# MicroDial_Data_Log_V2_Part2.net
KiCad netlist of a schematic drawn in Altium Designer
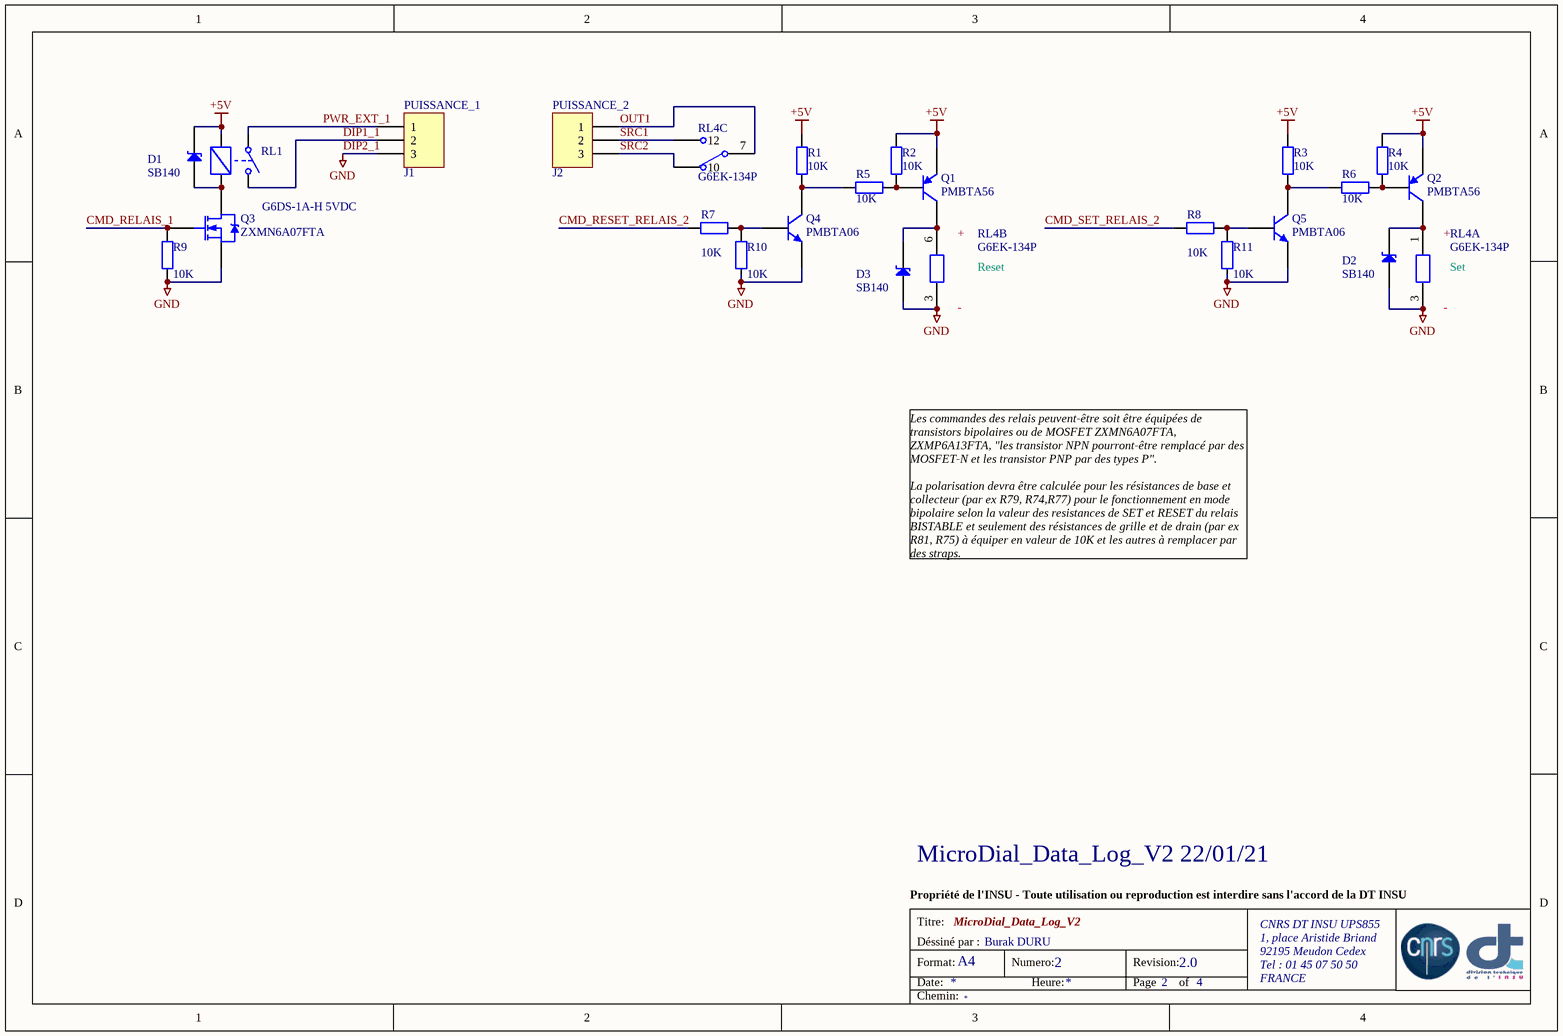
[diagram p0: MicroDial_Data_Log_V2_Part2.SchDoc]

(export (version "E")
  (design (tool "Eeschema 10.0.6"))
  (components
    (comp (ref "D1")
      (value "SB140")
      (footprint "DO-41")
      (description "SB140  Redresseur Schottky, 40 V, 1 A, Une, DO-41 (DO-204AL), 2 Broche(s), 500 mV")
      (libsource (lib "pSDLA") (part "Diode_Schottky"))
    )
    (comp (ref "D2")
      (value "SB140")
      (footprint "DO-41")
      (description "SB140  Redresseur Schottky, 40 V, 1 A, Une, DO-41 (DO-204AL), 2 Broche(s), 500 mV")
      (libsource (lib "pSDLA") (part "Diode_Schottky"))
    )
    (comp (ref "D3")
      (value "SB140")
      (footprint "DO-41")
      (description "SB140  Redresseur Schottky, 40 V, 1 A, Une, DO-41 (DO-204AL), 2 Broche(s), 500 mV")
      (libsource (lib "pSDLA") (part "Diode_Schottky"))
    )
    (comp (ref "J1")
      (value "PUISSANCE_1")
      (footprint "MKDS 1/3-3.81")
      (description "PHOENIX CONTACT MKDS 1/3-3.81  SR 3V DROIT")
      (libsource (lib "") (part "PHOENIX CONTACT MKDS 1/3-3.81_1"))
    )
    (comp (ref "J2")
      (value "PUISSANCE_2")
      (footprint "MKDS 1/3-3.81")
      (description "PHOENIX CONTACT MKDS 1/3-3.81  SR 3V DROIT")
      (libsource (lib "pSDLA") (part "PHOENIX CONTACT MKDS 1/3-3.81"))
    )
    (comp (ref "Q1")
      (value "PMBTA56")
      (footprint "PSDLA:SOT-23A")
      (description "PNP General Purpose Amplifier")
      (libsource (lib "pSDLA") (part "PMBTA56"))
    )
    (comp (ref "Q2")
      (value "PMBTA56")
      (footprint "PSDLA:SOT-23A")
      (description "PNP General Purpose Amplifier")
      (libsource (lib "pSDLA") (part "PMBTA56"))
    )
    (comp (ref "Q3")
      (value "ZXMN6A07FTA")
      (footprint "SOT23 - NMOSFET")
      (description "60V N-Channel ENHANCEMENT MODE MOSFET")
      (libsource (lib "pSDLA") (part "ZXMN6A07FTA"))
    )
    (comp (ref "Q4")
      (value "PMBTA06")
      (footprint "SOT-23A")
      (description "NPN General Purpose Amplifier")
      (libsource (lib "pSDLA") (part "PMBTA06"))
    )
    (comp (ref "Q5")
      (value "PMBTA06")
      (footprint "SOT-23A")
      (description "NPN General Purpose Amplifier")
      (libsource (lib "pSDLA") (part "PMBTA06"))
    )
    (comp (ref "R1")
      (value "10K")
      (footprint "R603")
      (fields (field (name "Comment") "Res"))
      (libsource (lib "pSDLA") (part "Res"))
    )
    (comp (ref "R2")
      (value "10K")
      (footprint "R603")
      (fields (field (name "Comment") "Res"))
      (libsource (lib "pSDLA") (part "Res"))
    )
    (comp (ref "R3")
      (value "10K")
      (footprint "R603")
      (fields (field (name "Comment") "Res"))
      (libsource (lib "pSDLA") (part "Res"))
    )
    (comp (ref "R4")
      (value "10K")
      (footprint "R603")
      (fields (field (name "Comment") "Res"))
      (libsource (lib "pSDLA") (part "Res"))
    )
    (comp (ref "R5")
      (value "10K")
      (footprint "R603")
      (fields (field (name "Comment") "Res"))
      (libsource (lib "") (part "Res_1"))
    )
    (comp (ref "R6")
      (value "10K")
      (footprint "R603")
      (fields (field (name "Comment") "Res"))
      (libsource (lib "") (part "Res_1"))
    )
    (comp (ref "R7")
      (value "10K")
      (footprint "R603")
      (fields (field (name "Comment") "Res"))
      (libsource (lib "") (part "Res_3"))
    )
    (comp (ref "R8")
      (value "10K")
      (footprint "R603")
      (fields (field (name "Comment") "Res"))
      (libsource (lib "") (part "Res_3"))
    )
    (comp (ref "R9")
      (value "10K")
      (footprint "R603")
      (fields (field (name "Comment") "Res"))
      (libsource (lib "") (part "Res_2"))
    )
    (comp (ref "R10")
      (value "10K")
      (footprint "R603")
      (fields (field (name "Comment") "Res"))
      (libsource (lib "") (part "Res_2"))
    )
    (comp (ref "R11")
      (value "10K")
      (footprint "R603")
      (fields (field (name "Comment") "Res"))
      (libsource (lib "") (part "Res_2"))
    )
    (comp (ref "RL1")
      (value "G6DS-1A-H 5VDC")
      (footprint "G6DS-1A-H")
      (description "Relais 1RT Normalement Ouvert 5V 5A")
      (libsource (lib "pSDLA") (part "G6DS-1A-H 5VDC"))
    )
    (comp (ref "RL4")
      (value "G6EK-134P")
      (footprint "G6EK-134P")
      (description "SPST RELAIS DOUBLE COIL")
      (libsource (lib "pSDLA") (part "G6EK-134P"))
    )
  )
  (nets
    (net (code "1") (name "+5V") (class "Default")
      (node (ref "D1") (pin "2") (pinfunction "K_2") (pintype "passive"))
      (node (ref "Q1") (pin "2") (pinfunction "E_2") (pintype "passive"))
      (node (ref "Q2") (pin "2") (pinfunction "E_2") (pintype "passive"))
      (node (ref "R1") (pin "1") (pinfunction "1_1") (pintype "passive"))
      (node (ref "R2") (pin "1") (pinfunction "1_1") (pintype "passive"))
      (node (ref "R3") (pin "1") (pinfunction "1_1") (pintype "passive"))
      (node (ref "R4") (pin "1") (pinfunction "1_1") (pintype "passive"))
      (node (ref "RL1") (pin "16") (pinfunction "16_16") (pintype "passive"))
    )
    (net (code "2") (name "/CMD_RELAIS_1") (class "Default")
      (node (ref "Q3") (pin "1") (pinfunction "G_1") (pintype "passive"))
      (node (ref "R9") (pin "2") (pinfunction "2_2") (pintype "passive"))
    )
    (net (code "3") (name "/CMD_RESET_RELAIS_2") (class "Default")
      (node (ref "R7") (pin "2") (pinfunction "2_2") (pintype "passive"))
    )
    (net (code "4") (name "/CMD_SET_RELAIS_2") (class "Default")
      (node (ref "R8") (pin "2") (pinfunction "2_2") (pintype "passive"))
    )
    (net (code "5") (name "/DIP1_1") (class "Default")
      (node (ref "J1") (pin "2") (pinfunction "2_2") (pintype "passive"))
      (node (ref "RL1") (pin "6") (pinfunction "6_6") (pintype "passive"))
    )
    (net (code "6") (name "/OUT1") (class "Default")
      (node (ref "J2") (pin "1") (pinfunction "1_1") (pintype "passive"))
      (node (ref "RL4") (pin "7") (pinfunction "7_7") (pintype "passive"))
    )
    (net (code "7") (name "/PWR_EXT_1") (class "Default")
      (node (ref "J1") (pin "1") (pinfunction "1_1") (pintype "passive"))
      (node (ref "RL1") (pin "8") (pinfunction "8_8") (pintype "passive"))
    )
    (net (code "8") (name "/SRC1") (class "Default")
      (node (ref "J2") (pin "2") (pinfunction "2_2") (pintype "passive"))
      (node (ref "RL4") (pin "12") (pinfunction "12_12") (pintype "passive"))
    )
    (net (code "9") (name "/SRC2") (class "Default")
      (node (ref "J2") (pin "3") (pinfunction "3_3") (pintype "passive"))
      (node (ref "RL4") (pin "10") (pinfunction "10_10") (pintype "passive"))
    )
    (net (code "10") (name "GND") (class "Default")
      (node (ref "D2") (pin "1") (pinfunction "A_1") (pintype "passive"))
      (node (ref "D3") (pin "1") (pinfunction "A_1") (pintype "passive"))
      (node (ref "J1") (pin "3") (pinfunction "3_3") (pintype "passive"))
      (node (ref "Q3") (pin "3") (pinfunction "S_3") (pintype "passive"))
      (node (ref "Q4") (pin "2") (pinfunction "E_2") (pintype "passive"))
      (node (ref "Q5") (pin "2") (pinfunction "E_2") (pintype "passive"))
      (node (ref "R10") (pin "1") (pinfunction "1_1") (pintype "passive"))
      (node (ref "R11") (pin "1") (pinfunction "1_1") (pintype "passive"))
      (node (ref "R9") (pin "1") (pinfunction "1_1") (pintype "passive"))
      (node (ref "RL4") (pin "3") (pinfunction "3_3") (pintype "passive"))
    )
    (net (code "11") (name "Net-(D1-A)") (class "Default")
      (node (ref "D1") (pin "1") (pinfunction "A_1") (pintype "passive"))
      (node (ref "Q3") (pin "2") (pinfunction "D_2") (pintype "passive"))
      (node (ref "RL1") (pin "15") (pinfunction "15_15") (pintype "passive"))
    )
    (net (code "12") (name "Net-(D2-K)") (class "Default")
      (node (ref "D2") (pin "2") (pinfunction "K_2") (pintype "passive"))
      (node (ref "Q2") (pin "3") (pinfunction "C_3") (pintype "passive"))
      (node (ref "RL4") (pin "1") (pinfunction "1_1") (pintype "passive"))
    )
    (net (code "13") (name "Net-(D3-K)") (class "Default")
      (node (ref "D3") (pin "2") (pinfunction "K_2") (pintype "passive"))
      (node (ref "Q1") (pin "3") (pinfunction "C_3") (pintype "passive"))
      (node (ref "RL4") (pin "6") (pinfunction "6_6") (pintype "passive"))
    )
    (net (code "14") (name "Net-(Q1-B)") (class "Default")
      (node (ref "Q1") (pin "1") (pinfunction "B_1") (pintype "passive"))
      (node (ref "R2") (pin "2") (pinfunction "2_2") (pintype "passive"))
      (node (ref "R5") (pin "2") (pinfunction "2_2") (pintype "passive"))
    )
    (net (code "15") (name "Net-(Q2-B)") (class "Default")
      (node (ref "Q2") (pin "1") (pinfunction "B_1") (pintype "passive"))
      (node (ref "R4") (pin "2") (pinfunction "2_2") (pintype "passive"))
      (node (ref "R6") (pin "2") (pinfunction "2_2") (pintype "passive"))
    )
    (net (code "16") (name "Net-(Q4-B)") (class "Default")
      (node (ref "Q4") (pin "1") (pinfunction "B_1") (pintype "passive"))
      (node (ref "R10") (pin "2") (pinfunction "2_2") (pintype "passive"))
      (node (ref "R7") (pin "1") (pinfunction "1_1") (pintype "passive"))
    )
    (net (code "17") (name "Net-(Q4-C)") (class "Default")
      (node (ref "Q4") (pin "3") (pinfunction "C_3") (pintype "passive"))
      (node (ref "R1") (pin "2") (pinfunction "2_2") (pintype "passive"))
      (node (ref "R5") (pin "1") (pinfunction "1_1") (pintype "passive"))
    )
    (net (code "18") (name "Net-(Q5-B)") (class "Default")
      (node (ref "Q5") (pin "1") (pinfunction "B_1") (pintype "passive"))
      (node (ref "R11") (pin "2") (pinfunction "2_2") (pintype "passive"))
      (node (ref "R8") (pin "1") (pinfunction "1_1") (pintype "passive"))
    )
    (net (code "19") (name "Net-(Q5-C)") (class "Default")
      (node (ref "Q5") (pin "3") (pinfunction "C_3") (pintype "passive"))
      (node (ref "R3") (pin "2") (pinfunction "2_2") (pintype "passive"))
      (node (ref "R6") (pin "1") (pinfunction "1_1") (pintype "passive"))
    )
  )
)
